# Schematic_v35.net
KiCad netlist of a schematic drawn in EAGLE
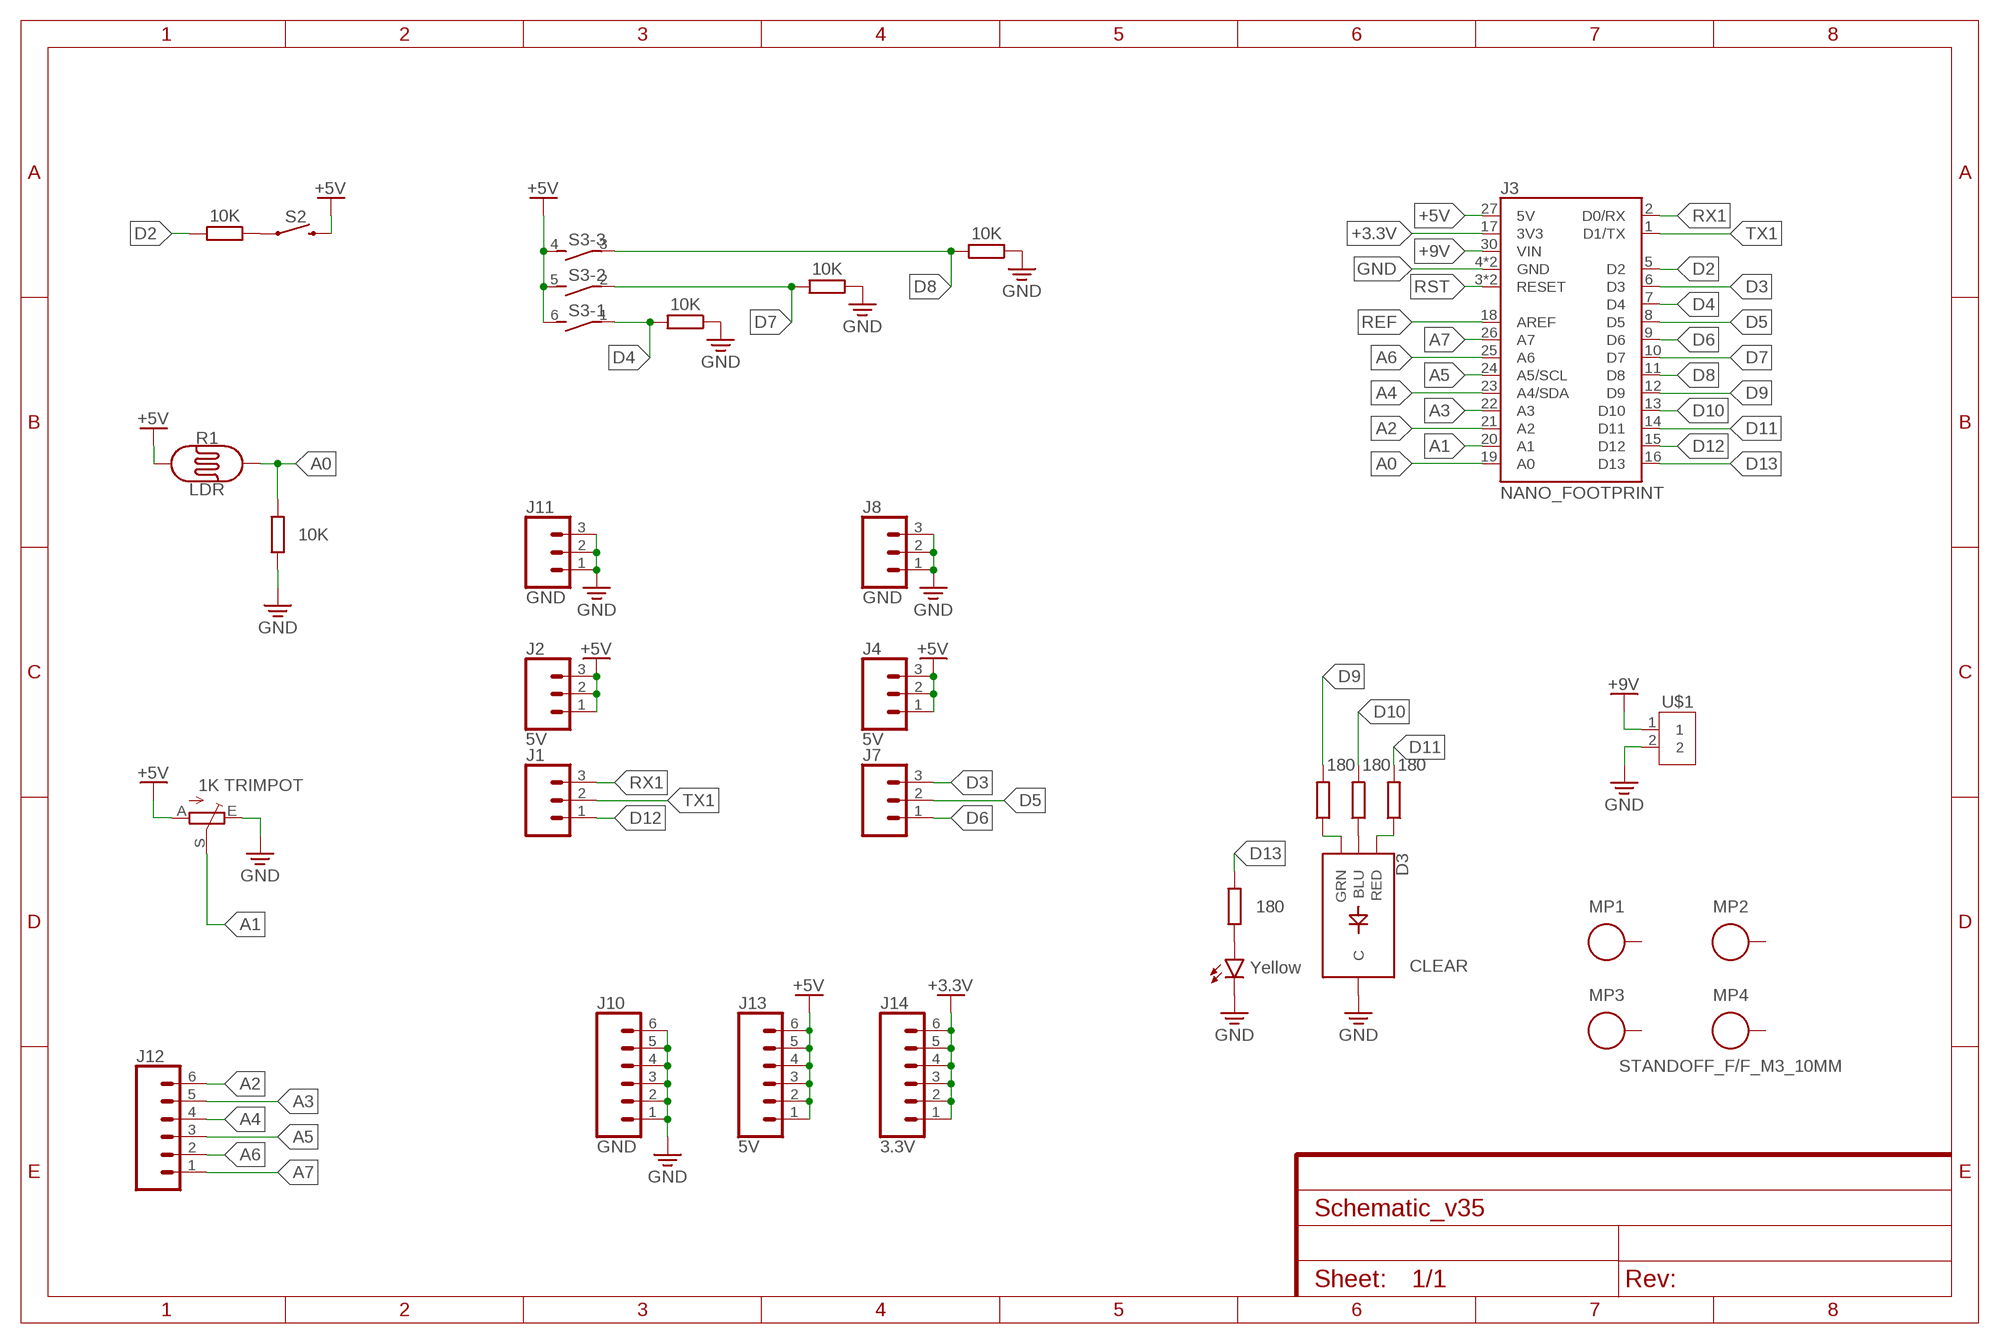
[diagram p0: schematic, sheet 1]

(export (version "E")
  (design (tool "Eeschema 10.0.6"))
  (components
    (comp (ref "D2")
      (value "Yellow")
      (footprint "eagle-import:LED_5MM")
      (libsource (lib "eagle-import") (part "LED5MM"))
    )
    (comp (ref "D3")
      (value "CLEAR")
      (footprint "eagle-import:LED-RGB-THRU")
      (libsource (lib "eagle-import") (part "LED-RGB-CCCLEAR"))
    )
    (comp (ref "J1")
      (value "CONN_03")
      (footprint "eagle-import:1X03")
      (libsource (lib "eagle-import") (part "CONN_03"))
    )
    (comp (ref "J2")
      (value "5V")
      (footprint "eagle-import:1X03")
      (libsource (lib "eagle-import") (part "CONN_03"))
    )
    (comp (ref "J3")
      (value "NANO_FOOTPRINT")
      (footprint "eagle-import:NANO")
      (libsource (lib "eagle-import") (part "NANO_FOOTPRINT"))
    )
    (comp (ref "J4")
      (value "5V")
      (footprint "eagle-import:1X03")
      (libsource (lib "eagle-import") (part "CONN_03"))
    )
    (comp (ref "J7")
      (value "CONN_03")
      (footprint "eagle-import:1X03")
      (libsource (lib "eagle-import") (part "CONN_03"))
    )
    (comp (ref "J8")
      (value "GND")
      (footprint "eagle-import:1X03")
      (libsource (lib "eagle-import") (part "CONN_03"))
    )
    (comp (ref "J10")
      (value "GND")
      (footprint "eagle-import:1X06")
      (libsource (lib "eagle-import") (part "CONN_06SILK_FEMALE_PTH"))
    )
    (comp (ref "J11")
      (value "GND")
      (footprint "eagle-import:1X03")
      (libsource (lib "eagle-import") (part "CONN_03"))
    )
    (comp (ref "J12")
      (value "CONN_06SILK_FEMALE_PTH")
      (footprint "eagle-import:1X06")
      (libsource (lib "eagle-import") (part "SparkFun-Connectors_513_CONN_06SILK_FEMALE_PTH"))
    )
    (comp (ref "J13")
      (value "5V")
      (footprint "eagle-import:1X06")
      (libsource (lib "eagle-import") (part "CONN_06SILK_FEMALE_PTH"))
    )
    (comp (ref "J14")
      (value "3.3V")
      (footprint "eagle-import:1X06")
      (libsource (lib "eagle-import") (part "CONN_06SILK_FEMALE_PTH"))
    )
    (comp (ref "MP1")
      (value "STANDOFF_F/F_M3_10MM")
      (footprint "eagle-import:STANDOFF_HEX_FEMALE_550X1000_M3X0.5_MTGP850H320")
      (libsource (lib "eagle-import") (part "STANDOFF_F/FM3_10MM_"))
    )
    (comp (ref "MP2")
      (value "STANDOFF_F/F_M3_10MM")
      (footprint "eagle-import:STANDOFF_HEX_FEMALE_550X1000_M3X0.5_MTGP850H320")
      (libsource (lib "eagle-import") (part "STANDOFF_F/FM3_10MM_"))
    )
    (comp (ref "MP3")
      (value "STANDOFF_F/F_M3_10MM")
      (footprint "eagle-import:STANDOFF_HEX_FEMALE_550X1000_M3X0.5_MTGP850H320")
      (libsource (lib "eagle-import") (part "STANDOFF_F/FM3_10MM_"))
    )
    (comp (ref "MP4")
      (value "STANDOFF_F/F_M3_10MM")
      (footprint "eagle-import:STANDOFF_HEX_FEMALE_550X1000_M3X0.5_MTGP850H320")
      (libsource (lib "eagle-import") (part "STANDOFF_F/FM3_10MM_"))
    )
    (comp (ref "R1")
      (value "LDR")
      (footprint "eagle-import:PHOTOCELL-KIT")
      (libsource (lib "eagle-import") (part "PHOTOCELLPTH-KIT"))
    )
    (comp (ref "R3")
      (value "180")
      (footprint "eagle-import:RESAD724W46L381D178B")
      (libsource (lib "eagle-import") (part "RAXIAL-7.2MM-PITCH_"))
    )
    (comp (ref "R4")
      (value "1K TRIMPOT")
      (footprint "eagle-import:B25P")
      (libsource (lib "eagle-import") (part "TRIM_EU-B25P"))
    )
    (comp (ref "R5")
      (value "10K")
      (footprint "eagle-import:RESAD724W46L381D178B")
      (libsource (lib "eagle-import") (part "RAXIAL-7.2MM-PITCH_"))
    )
    (comp (ref "R6")
      (value "180")
      (footprint "eagle-import:RESAD724W46L381D178B")
      (libsource (lib "eagle-import") (part "RAXIAL-7.2MM-PITCH_"))
    )
    (comp (ref "R7")
      (value "180")
      (footprint "eagle-import:RESAD724W46L381D178B")
      (libsource (lib "eagle-import") (part "RAXIAL-7.2MM-PITCH_"))
    )
    (comp (ref "R8")
      (value "180")
      (footprint "eagle-import:RESAD724W46L381D178B")
      (libsource (lib "eagle-import") (part "RAXIAL-7.2MM-PITCH_"))
    )
    (comp (ref "R9")
      (value "10K")
      (footprint "eagle-import:RESAD724W46L381D178B")
      (libsource (lib "eagle-import") (part "RAXIAL-7.2MM-PITCH_"))
    )
    (comp (ref "R10")
      (value "10K")
      (footprint "eagle-import:RESAD724W46L381D178B")
      (libsource (lib "eagle-import") (part "RAXIAL-7.2MM-PITCH_"))
    )
    (comp (ref "R11")
      (value "10K")
      (footprint "eagle-import:RESAD724W46L381D178B")
      (libsource (lib "eagle-import") (part "RAXIAL-7.2MM-PITCH_"))
    )
    (comp (ref "R12")
      (value "10K")
      (footprint "eagle-import:RESAD724W46L381D178B")
      (libsource (lib "eagle-import") (part "RAXIAL-7.2MM-PITCH_"))
    )
    (comp (ref "S2")
      (value "BUTTON")
      (footprint "eagle-import:TACTILE_SWITCH_PTH_6.0MM_KIT")
      (libsource (lib "eagle-import") (part "MOMENTARY-SWITCH-SPST-PTH-6.0MM-KIT"))
    )
    (comp (ref "S3")
      (value "DIP SWITCH")
      (footprint "eagle-import:DS-03")
      (libsource (lib "eagle-import") (part "DS03E"))
    )
    (comp (ref "U$1")
      (value "2828XX-2282837-2")
      (footprint "eagle-import:TERMBLK_508-2N")
      (fields (field (name "MANUFACTURER") "TE Connectivity") (field (name "MPN") "282837-2"))
      (libsource (lib "eagle-import") (part "2828XX-2282837-2"))
    )
  )
  (nets
    (net (code "1") (name "+3.3V") (class "Default")
      (node (ref "J14") (pin "1") (pinfunction "1_1") (pintype "passive"))
      (node (ref "J14") (pin "2") (pinfunction "2_2") (pintype "passive"))
      (node (ref "J14") (pin "3") (pinfunction "3_3") (pintype "passive"))
      (node (ref "J14") (pin "4") (pinfunction "4_4") (pintype "passive"))
      (node (ref "J14") (pin "5") (pinfunction "5_5") (pintype "passive"))
      (node (ref "J14") (pin "6") (pinfunction "6_6") (pintype "passive"))
      (node (ref "J3") (pin "17") (pinfunction "3V3_17") (pintype "bidirectional"))
    )
    (net (code "2") (name "+5V") (class "Default")
      (node (ref "J13") (pin "1") (pinfunction "1_1") (pintype "passive"))
      (node (ref "J13") (pin "2") (pinfunction "2_2") (pintype "passive"))
      (node (ref "J13") (pin "3") (pinfunction "3_3") (pintype "passive"))
      (node (ref "J13") (pin "4") (pinfunction "4_4") (pintype "passive"))
      (node (ref "J13") (pin "5") (pinfunction "5_5") (pintype "passive"))
      (node (ref "J13") (pin "6") (pinfunction "6_6") (pintype "passive"))
      (node (ref "J2") (pin "1") (pinfunction "1_1") (pintype "passive"))
      (node (ref "J2") (pin "2") (pinfunction "2_2") (pintype "passive"))
      (node (ref "J2") (pin "3") (pinfunction "3_3") (pintype "passive"))
      (node (ref "J3") (pin "27") (pinfunction "5V_27") (pintype "bidirectional"))
      (node (ref "J4") (pin "1") (pinfunction "1_1") (pintype "passive"))
      (node (ref "J4") (pin "2") (pinfunction "2_2") (pintype "passive"))
      (node (ref "J4") (pin "3") (pinfunction "3_3") (pintype "passive"))
      (node (ref "R1") (pin "1") (pinfunction "P$1_1") (pintype "bidirectional"))
      (node (ref "R4") (pin "A") (pinfunction "A_A") (pintype "passive"))
      (node (ref "S2") (pin "3") (pinfunction "2_3") (pintype "passive"))
      (node (ref "S3") (pin "4") (pinfunction "2_4") (pintype "passive"))
      (node (ref "S3") (pin "5") (pinfunction "2_5") (pintype "passive"))
      (node (ref "S3") (pin "6") (pinfunction "2_6") (pintype "passive"))
    )
    (net (code "3") (name "+9V") (class "Default")
      (node (ref "J3") (pin "30") (pinfunction "VIN_30") (pintype "bidirectional"))
      (node (ref "U$1") (pin "1") (pinfunction "1_1") (pintype "bidirectional"))
    )
    (net (code "4") (name "A0") (class "Default")
      (node (ref "J3") (pin "19") (pinfunction "A0_19") (pintype "bidirectional"))
      (node (ref "R1") (pin "2") (pinfunction "P$2_2") (pintype "bidirectional"))
      (node (ref "R9") (pin "2") (pinfunction "2_2") (pintype "passive"))
    )
    (net (code "5") (name "A1") (class "Default")
      (node (ref "J3") (pin "20") (pinfunction "A1_20") (pintype "bidirectional"))
      (node (ref "R4") (pin "S") (pinfunction "S_S") (pintype "passive"))
    )
    (net (code "6") (name "A2") (class "Default")
      (node (ref "J12") (pin "6") (pinfunction "6_6") (pintype "passive"))
      (node (ref "J3") (pin "21") (pinfunction "A2_21") (pintype "bidirectional"))
    )
    (net (code "7") (name "A3") (class "Default")
      (node (ref "J12") (pin "5") (pinfunction "5_5") (pintype "passive"))
      (node (ref "J3") (pin "22") (pinfunction "A3_22") (pintype "bidirectional"))
    )
    (net (code "8") (name "A4") (class "Default")
      (node (ref "J12") (pin "4") (pinfunction "4_4") (pintype "passive"))
      (node (ref "J3") (pin "23") (pinfunction "A4/SDA_23") (pintype "bidirectional"))
    )
    (net (code "9") (name "A5") (class "Default")
      (node (ref "J12") (pin "3") (pinfunction "3_3") (pintype "passive"))
      (node (ref "J3") (pin "24") (pinfunction "A5/SCL_24") (pintype "bidirectional"))
    )
    (net (code "10") (name "A6") (class "Default")
      (node (ref "J12") (pin "2") (pinfunction "2_2") (pintype "passive"))
      (node (ref "J3") (pin "25") (pinfunction "A6_25") (pintype "bidirectional"))
    )
    (net (code "11") (name "A7") (class "Default")
      (node (ref "J12") (pin "1") (pinfunction "1_1") (pintype "passive"))
      (node (ref "J3") (pin "26") (pinfunction "A7_26") (pintype "bidirectional"))
    )
    (net (code "12") (name "D2") (class "Default")
      (node (ref "J3") (pin "5") (pinfunction "D2_5") (pintype "bidirectional"))
      (node (ref "R5") (pin "2") (pinfunction "2_2") (pintype "passive"))
    )
    (net (code "13") (name "D3") (class "Default")
      (node (ref "J3") (pin "6") (pinfunction "D3_6") (pintype "bidirectional"))
      (node (ref "J7") (pin "3") (pinfunction "3_3") (pintype "passive"))
    )
    (net (code "14") (name "D4") (class "Default")
      (node (ref "J3") (pin "7") (pinfunction "D4_7") (pintype "bidirectional"))
      (node (ref "R12") (pin "2") (pinfunction "2_2") (pintype "passive"))
      (node (ref "S3") (pin "1") (pinfunction "1_1") (pintype "passive"))
    )
    (net (code "15") (name "D5") (class "Default")
      (node (ref "J3") (pin "8") (pinfunction "D5_8") (pintype "bidirectional"))
      (node (ref "J7") (pin "2") (pinfunction "2_2") (pintype "passive"))
    )
    (net (code "16") (name "D6") (class "Default")
      (node (ref "J3") (pin "9") (pinfunction "D6_9") (pintype "bidirectional"))
      (node (ref "J7") (pin "1") (pinfunction "1_1") (pintype "passive"))
    )
    (net (code "17") (name "D7") (class "Default")
      (node (ref "J3") (pin "10") (pinfunction "D7_10") (pintype "bidirectional"))
      (node (ref "R11") (pin "2") (pinfunction "2_2") (pintype "passive"))
      (node (ref "S3") (pin "2") (pinfunction "1_2") (pintype "passive"))
    )
    (net (code "18") (name "D8") (class "Default")
      (node (ref "J3") (pin "11") (pinfunction "D8_11") (pintype "bidirectional"))
      (node (ref "R10") (pin "2") (pinfunction "2_2") (pintype "passive"))
      (node (ref "S3") (pin "3") (pinfunction "1_3") (pintype "passive"))
    )
    (net (code "19") (name "D9") (class "Default")
      (node (ref "J3") (pin "12") (pinfunction "D9_12") (pintype "bidirectional"))
      (node (ref "R6") (pin "2") (pinfunction "2_2") (pintype "passive"))
    )
    (net (code "20") (name "D10") (class "Default")
      (node (ref "J3") (pin "13") (pinfunction "D10_13") (pintype "bidirectional"))
      (node (ref "R7") (pin "2") (pinfunction "2_2") (pintype "passive"))
    )
    (net (code "21") (name "D11") (class "Default")
      (node (ref "J3") (pin "14") (pinfunction "D11_14") (pintype "bidirectional"))
      (node (ref "R8") (pin "2") (pinfunction "2_2") (pintype "passive"))
    )
    (net (code "22") (name "D12") (class "Default")
      (node (ref "J1") (pin "1") (pinfunction "1_1") (pintype "passive"))
      (node (ref "J3") (pin "15") (pinfunction "D12_15") (pintype "bidirectional"))
    )
    (net (code "23") (name "D13") (class "Default")
      (node (ref "J3") (pin "16") (pinfunction "D13_16") (pintype "bidirectional"))
      (node (ref "R3") (pin "2") (pinfunction "2_2") (pintype "passive"))
    )
    (net (code "24") (name "GND") (class "Default")
      (node (ref "D2") (pin "K") (pinfunction "C_K") (pintype "passive"))
      (node (ref "D3") (pin "2") (pinfunction "C_2") (pintype "bidirectional"))
      (node (ref "J10") (pin "1") (pinfunction "1_1") (pintype "passive"))
      (node (ref "J10") (pin "2") (pinfunction "2_2") (pintype "passive"))
      (node (ref "J10") (pin "3") (pinfunction "3_3") (pintype "passive"))
      (node (ref "J10") (pin "4") (pinfunction "4_4") (pintype "passive"))
      (node (ref "J10") (pin "5") (pinfunction "5_5") (pintype "passive"))
      (node (ref "J10") (pin "6") (pinfunction "6_6") (pintype "passive"))
      (node (ref "J11") (pin "1") (pinfunction "1_1") (pintype "passive"))
      (node (ref "J11") (pin "2") (pinfunction "2_2") (pintype "passive"))
      (node (ref "J11") (pin "3") (pinfunction "3_3") (pintype "passive"))
      (node (ref "J3") (pin "29") (pinfunction "GND_29") (pintype "bidirectional"))
      (node (ref "J3") (pin "4") (pinfunction "GND_4") (pintype "bidirectional"))
      (node (ref "J8") (pin "1") (pinfunction "1_1") (pintype "passive"))
      (node (ref "J8") (pin "2") (pinfunction "2_2") (pintype "passive"))
      (node (ref "J8") (pin "3") (pinfunction "3_3") (pintype "passive"))
      (node (ref "R10") (pin "1") (pinfunction "1_1") (pintype "passive"))
      (node (ref "R11") (pin "1") (pinfunction "1_1") (pintype "passive"))
      (node (ref "R12") (pin "1") (pinfunction "1_1") (pintype "passive"))
      (node (ref "R4") (pin "E") (pinfunction "E_E") (pintype "passive"))
      (node (ref "R9") (pin "1") (pinfunction "1_1") (pintype "passive"))
      (node (ref "U$1") (pin "2") (pinfunction "2_2") (pintype "bidirectional"))
    )
    (net (code "25") (name "Net-(D2-PadA)") (class "Default")
      (node (ref "D2") (pin "A") (pinfunction "A_A") (pintype "passive"))
      (node (ref "R3") (pin "1") (pinfunction "1_1") (pintype "passive"))
    )
    (net (code "26") (name "Net-(D3-BLU)") (class "Default")
      (node (ref "D3") (pin "4") (pinfunction "BLU_4") (pintype "bidirectional"))
      (node (ref "R7") (pin "1") (pinfunction "1_1") (pintype "passive"))
    )
    (net (code "27") (name "Net-(D3-GRN)") (class "Default")
      (node (ref "D3") (pin "3") (pinfunction "GRN_3") (pintype "bidirectional"))
      (node (ref "R6") (pin "1") (pinfunction "1_1") (pintype "passive"))
    )
    (net (code "28") (name "Net-(D3-RED)") (class "Default")
      (node (ref "D3") (pin "1") (pinfunction "RED_1") (pintype "bidirectional"))
      (node (ref "R8") (pin "1") (pinfunction "1_1") (pintype "passive"))
    )
    (net (code "29") (name "Net-(R5-Pad1)") (class "Default")
      (node (ref "R5") (pin "1") (pinfunction "1_1") (pintype "passive"))
      (node (ref "S2") (pin "1") (pinfunction "1_1") (pintype "passive"))
    )
    (net (code "30") (name "REF") (class "Default")
      (node (ref "J3") (pin "18") (pinfunction "AREF_18") (pintype "bidirectional"))
    )
    (net (code "31") (name "RST") (class "Default")
      (node (ref "J3") (pin "28") (pinfunction "RESET_28") (pintype "bidirectional"))
      (node (ref "J3") (pin "3") (pinfunction "RESET_3") (pintype "bidirectional"))
    )
    (net (code "32") (name "RX1") (class "Default")
      (node (ref "J1") (pin "3") (pinfunction "3_3") (pintype "passive"))
      (node (ref "J3") (pin "2") (pinfunction "D0/RX_2") (pintype "bidirectional"))
    )
    (net (code "33") (name "TX1") (class "Default")
      (node (ref "J1") (pin "2") (pinfunction "2_2") (pintype "passive"))
      (node (ref "J3") (pin "1") (pinfunction "D1/TX_1") (pintype "bidirectional"))
    )
    (net (code "34") (name "unconnected-(MP1-P$1-Pad1)") (class "Default")
      (node (ref "MP1") (pin "1") (pinfunction "P$1_1") (pintype "passive"))
    )
    (net (code "35") (name "unconnected-(MP2-P$1-Pad1)") (class "Default")
      (node (ref "MP2") (pin "1") (pinfunction "P$1_1") (pintype "passive"))
    )
    (net (code "36") (name "unconnected-(MP3-P$1-Pad1)") (class "Default")
      (node (ref "MP3") (pin "1") (pinfunction "P$1_1") (pintype "passive"))
    )
    (net (code "37") (name "unconnected-(MP4-P$1-Pad1)") (class "Default")
      (node (ref "MP4") (pin "1") (pinfunction "P$1_1") (pintype "passive"))
    )
  )
)
